# untitled.net
KiCad netlist of a schematic drawn in EAGLE
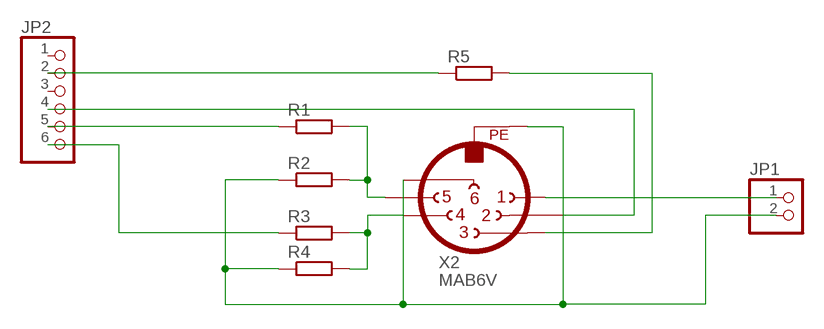
[diagram p0: schematic, sheet 1]

(export (version "E")
  (design (tool "Eeschema 10.0.6"))
  (components
    (comp (ref "JP1")
      (value "PINHD-1X2")
      (footprint "eagle-import:1X02")
      (libsource (lib "eagle-import") (part "PINHD-1X2"))
    )
    (comp (ref "JP2")
      (value "PINHD-1X6")
      (footprint "eagle-import:1X06")
      (libsource (lib "eagle-import") (part "PINHD-1X6"))
    )
    (comp (ref "R1")
      (value "R-EU_0204/7")
      (footprint "eagle-import:0204_7")
      (libsource (lib "eagle-import") (part "R-EU_0204/7"))
    )
    (comp (ref "R2")
      (value "R-EU_0204/7")
      (footprint "eagle-import:0204_7")
      (libsource (lib "eagle-import") (part "R-EU_0204/7"))
    )
    (comp (ref "R3")
      (value "R-EU_0204/7")
      (footprint "eagle-import:0204_7")
      (libsource (lib "eagle-import") (part "R-EU_0204/7"))
    )
    (comp (ref "R4")
      (value "R-EU_0204/7")
      (footprint "eagle-import:0204_7")
      (libsource (lib "eagle-import") (part "R-EU_0204/7"))
    )
    (comp (ref "R5")
      (value "R-EU_0207/15")
      (footprint "eagle-import:0207_15")
      (libsource (lib "eagle-import") (part "R-EU_0207/15"))
    )
    (comp (ref "X2")
      (value "MAB6V")
      (footprint "eagle-import:MAB6V")
      (libsource (lib "eagle-import") (part "MAB6V"))
    )
  )
  (nets
    (net (code "1") (name "Net-(JP1-Pad1)") (class "Default")
      (node (ref "JP1") (pin "1") (pinfunction "1_1") (pintype "passive"))
      (node (ref "X2") (pin "1") (pinfunction "1_1") (pintype "passive"))
    )
    (net (code "2") (name "Net-(JP1-Pad2)") (class "Default")
      (node (ref "JP1") (pin "2") (pinfunction "2_2") (pintype "passive"))
      (node (ref "R2") (pin "1") (pinfunction "1_1") (pintype "passive"))
      (node (ref "R4") (pin "1") (pinfunction "1_1") (pintype "passive"))
      (node (ref "X2") (pin "6") (pinfunction "6_6") (pintype "passive"))
      (node (ref "X2") (pin "PE") (pinfunction "PE_PE") (pintype "power_in"))
    )
    (net (code "3") (name "Net-(JP2-Pad2)") (class "Default")
      (node (ref "JP2") (pin "2") (pinfunction "2_2") (pintype "passive"))
      (node (ref "R5") (pin "1") (pinfunction "1_1") (pintype "passive"))
    )
    (net (code "4") (name "Net-(JP2-Pad4)") (class "Default")
      (node (ref "JP2") (pin "4") (pinfunction "4_4") (pintype "passive"))
      (node (ref "X2") (pin "2") (pinfunction "2_2") (pintype "passive"))
    )
    (net (code "5") (name "Net-(JP2-Pad5)") (class "Default")
      (node (ref "JP2") (pin "5") (pinfunction "5_5") (pintype "passive"))
      (node (ref "R1") (pin "1") (pinfunction "1_1") (pintype "passive"))
    )
    (net (code "6") (name "Net-(JP2-Pad6)") (class "Default")
      (node (ref "JP2") (pin "6") (pinfunction "6_6") (pintype "passive"))
      (node (ref "R3") (pin "1") (pinfunction "1_1") (pintype "passive"))
    )
    (net (code "7") (name "Net-(R1-Pad2)") (class "Default")
      (node (ref "R1") (pin "2") (pinfunction "2_2") (pintype "passive"))
      (node (ref "R2") (pin "2") (pinfunction "2_2") (pintype "passive"))
      (node (ref "X2") (pin "5") (pinfunction "5_5") (pintype "passive"))
    )
    (net (code "8") (name "Net-(R3-Pad2)") (class "Default")
      (node (ref "R3") (pin "2") (pinfunction "2_2") (pintype "passive"))
      (node (ref "R4") (pin "2") (pinfunction "2_2") (pintype "passive"))
      (node (ref "X2") (pin "4") (pinfunction "4_4") (pintype "passive"))
    )
    (net (code "9") (name "Net-(R5-Pad2)") (class "Default")
      (node (ref "R5") (pin "2") (pinfunction "2_2") (pintype "passive"))
      (node (ref "X2") (pin "3") (pinfunction "3_3") (pintype "passive"))
    )
    (net (code "10") (name "unconnected-(JP2-Pad1)") (class "Default")
      (node (ref "JP2") (pin "1") (pinfunction "1_1") (pintype "passive"))
    )
    (net (code "11") (name "unconnected-(JP2-Pad3)") (class "Default")
      (node (ref "JP2") (pin "3") (pinfunction "3_3") (pintype "passive"))
    )
  )
)
